# OctoSlime_Haptics_LED_Driver_Imported.net
KiCad netlist of a schematic drawn in EasyEDA Pro
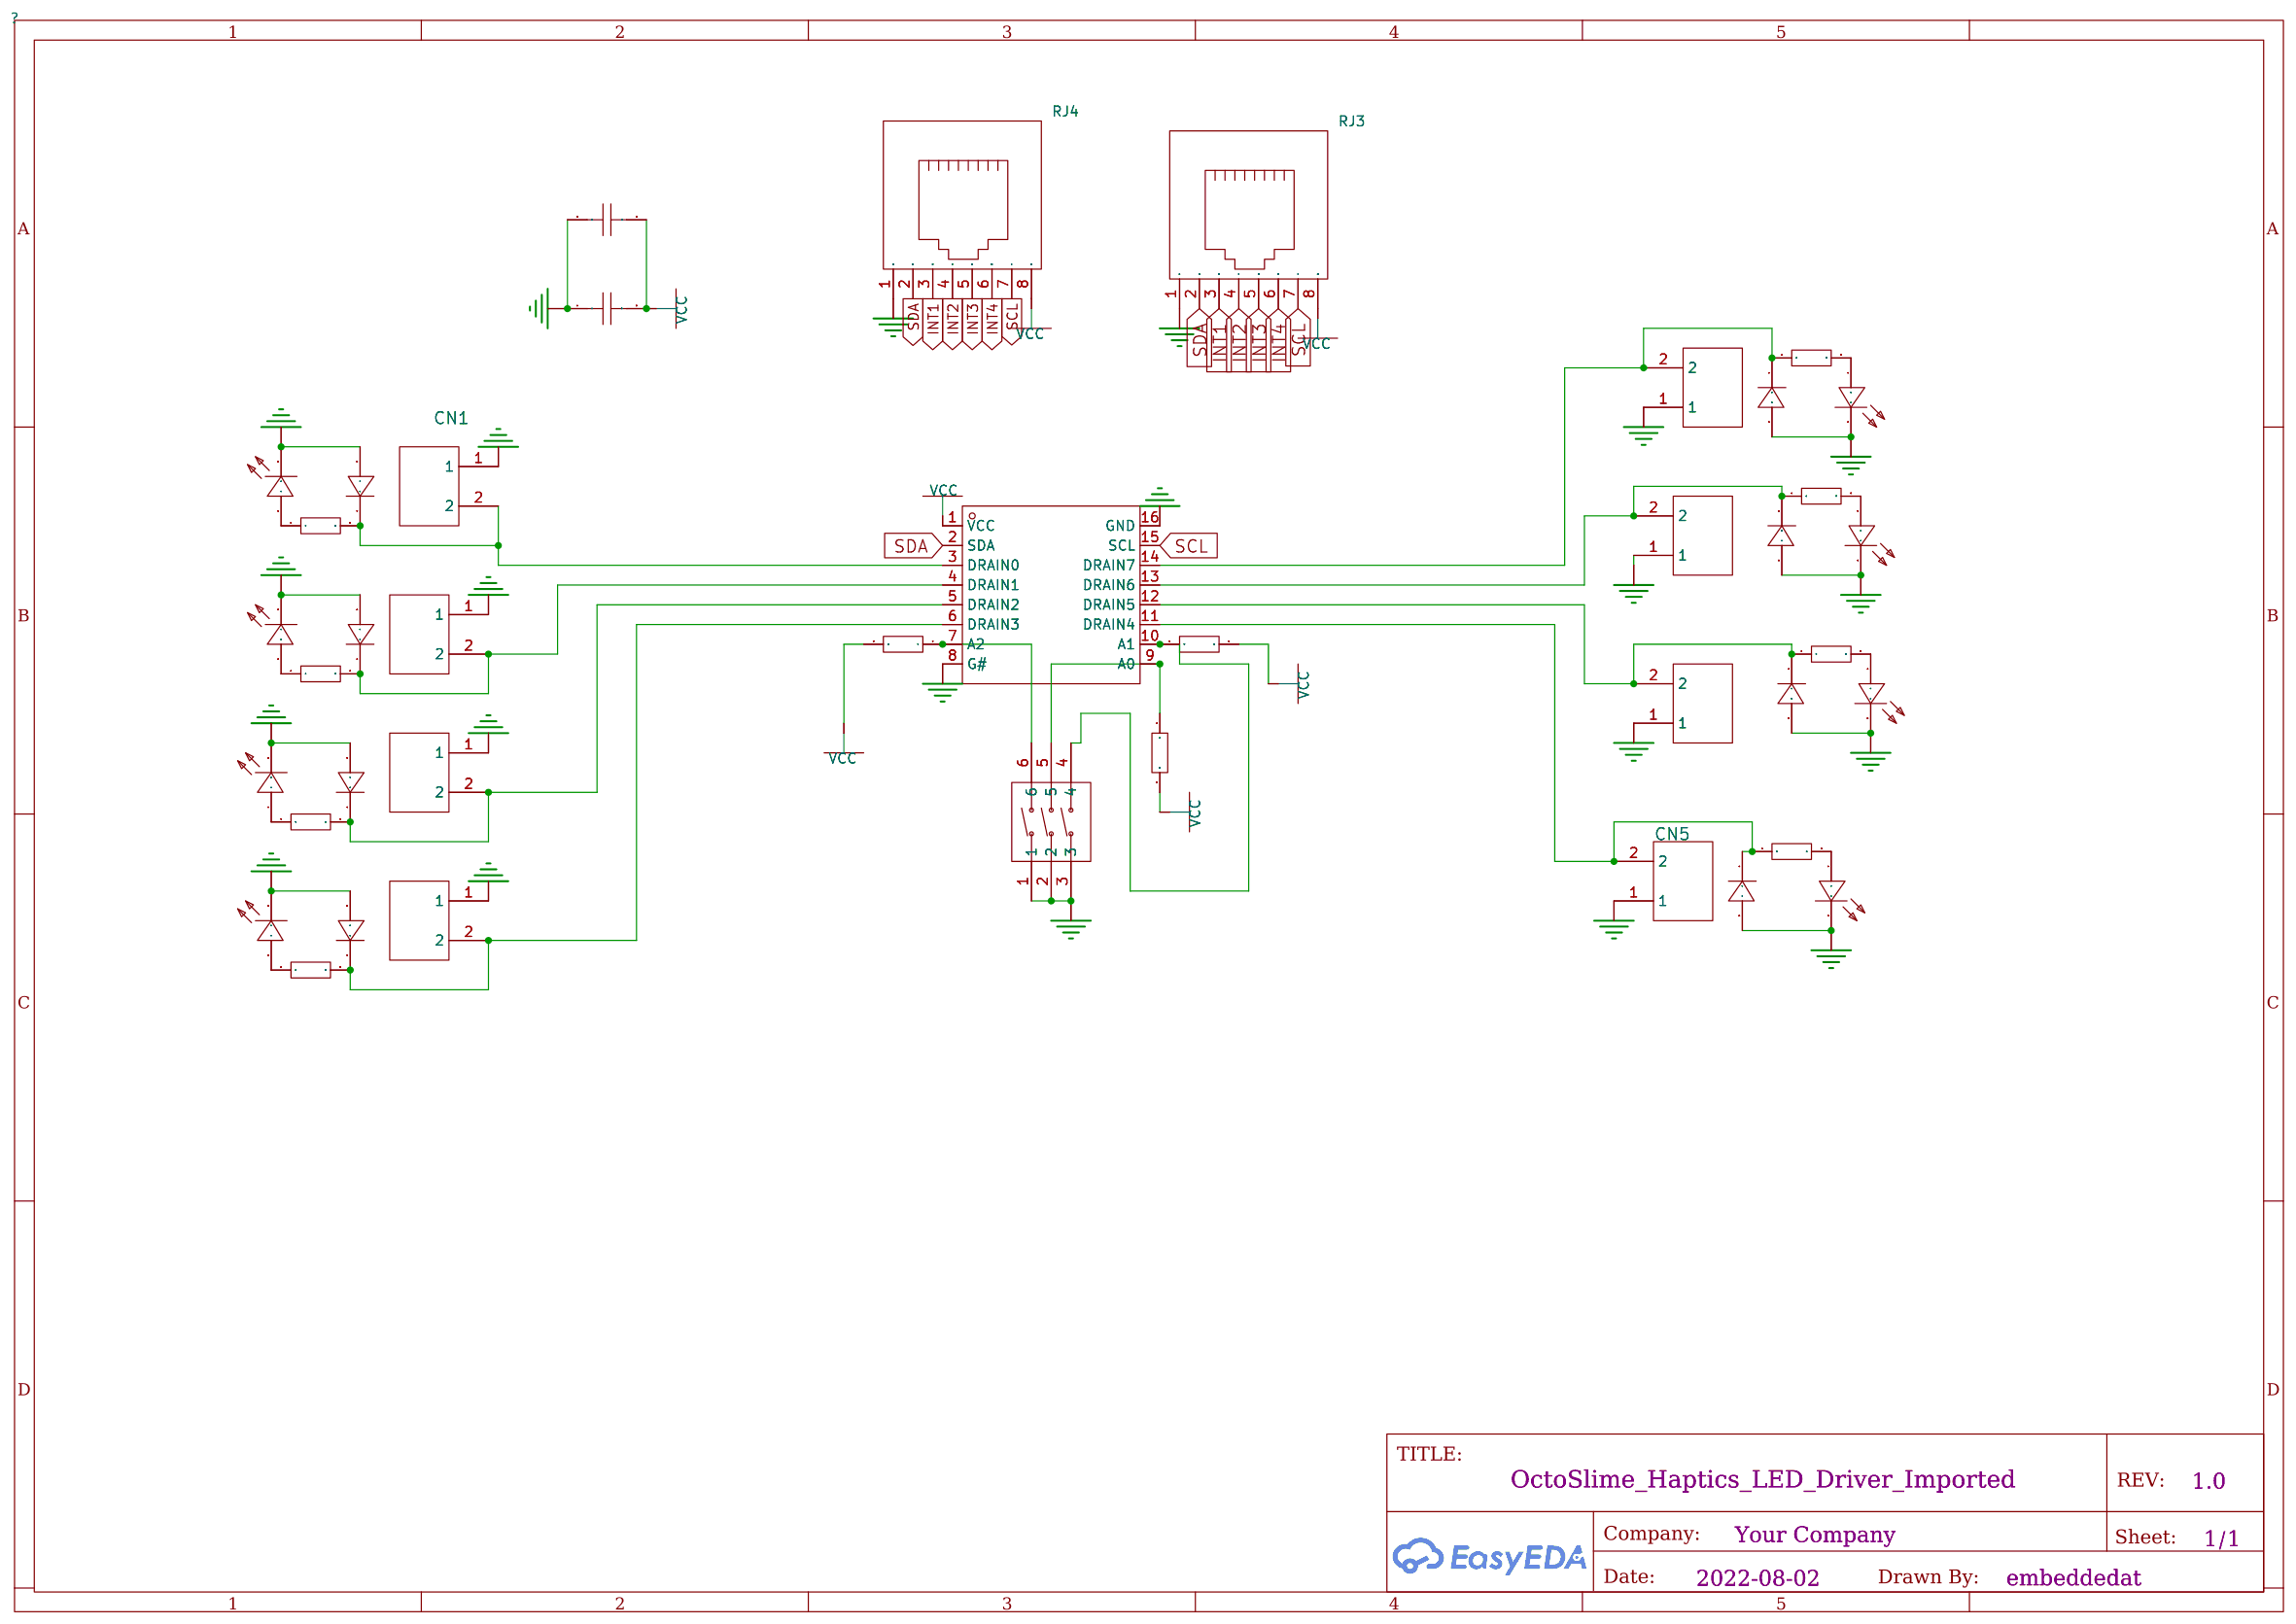
[diagram p0: schematic sheet]

(export (version "E")
  (design (tool "Eeschema 10.0.6"))
  (components
    (comp (ref "C3")
      (value "47uF")
      (footprint "easyedapro:C1206")
      (description "容值:47uF;精度:±20%;额定电压:10V;温度系数:X5R;")
      (fields
        (field (name "Manufacturer Part") "CL31A476MPHNNNE")
        (field (name "Manufacturer") "SAMSUNG(三星)")
      )
      (libsource (lib "easyedapro") (part "CL31A476MPHNNNE"))
    )
    (comp (ref "C4")
      (value "100nF")
      (footprint "easyedapro:C0402")
      (description "容值:100nF;精度:±10%;额定电压:50V;温度系数:X7R;")
      (fields
        (field (name "Manufacturer Part") "CL05B104KB54PNC")
        (field (name "Manufacturer") "SAMSUNG(三星)")
      )
      (libsource (lib "easyedapro") (part "CL05B104KB54PNC"))
    )
    (comp (ref "CN1")
      (value "B2B-PH-K-S(LF)(SN)")
      (footprint "easyedapro:CONN-TH_B2B-PH-K-S")
      (fields (field (name "Manufacturer") "JST"))
      (libsource (lib "easyedapro") (part "B2B-PH-K-S(LF)(SN)"))
    )
    (comp (ref "CN2")
      (value "B2B-PH-K-S(LF)(SN)")
      (footprint "easyedapro:CONN-TH_B2B-PH-K-S")
      (fields (field (name "Manufacturer") "JST"))
      (libsource (lib "easyedapro") (part "B2B-PH-K-S(LF)(SN)"))
    )
    (comp (ref "CN3")
      (value "B2B-PH-K-S(LF)(SN)")
      (footprint "easyedapro:CONN-TH_B2B-PH-K-S")
      (fields (field (name "Manufacturer") "JST"))
      (libsource (lib "easyedapro") (part "B2B-PH-K-S(LF)(SN)"))
    )
    (comp (ref "CN4")
      (value "B2B-PH-K-S(LF)(SN)")
      (footprint "easyedapro:CONN-TH_B2B-PH-K-S")
      (fields (field (name "Manufacturer") "JST"))
      (libsource (lib "easyedapro") (part "B2B-PH-K-S(LF)(SN)"))
    )
    (comp (ref "CN5")
      (value "B2B-PH-K-S(LF)(SN)")
      (footprint "easyedapro:CONN-TH_B2B-PH-K-S")
      (fields (field (name "Manufacturer") "JST"))
      (libsource (lib "easyedapro") (part "B2B-PH-K-S(LF)(SN)"))
    )
    (comp (ref "CN6")
      (value "B2B-PH-K-S(LF)(SN)")
      (footprint "easyedapro:CONN-TH_B2B-PH-K-S")
      (fields (field (name "Manufacturer") "JST"))
      (libsource (lib "easyedapro") (part "B2B-PH-K-S(LF)(SN)"))
    )
    (comp (ref "CN7")
      (value "B2B-PH-K-S(LF)(SN)")
      (footprint "easyedapro:CONN-TH_B2B-PH-K-S")
      (fields (field (name "Manufacturer") "JST"))
      (libsource (lib "easyedapro") (part "B2B-PH-K-S(LF)(SN)"))
    )
    (comp (ref "CN8")
      (value "B2B-PH-K-S(LF)(SN)")
      (footprint "easyedapro:CONN-TH_B2B-PH-K-S")
      (fields (field (name "Manufacturer") "JST"))
      (libsource (lib "easyedapro") (part "B2B-PH-K-S(LF)(SN)"))
    )
    (comp (ref "D9")
      (value "~")
      (footprint "easyedapro:DO-214AC_L4.3-W2.7-LS5.3-RD")
      (description "二极管配置:-;直流反向耐压(Vr):1kV;平均整流电流(Io):1A;正向压降(Vf):1.1V@1A;反向电流(Ir):5A@1kV;")
      (fields (field (name "Manufacturer Part") "M7") (field (name "Manufacturer") "MDD"))
      (libsource (lib "easyedapro") (part "M7_C95872"))
    )
    (comp (ref "D10")
      (value "~")
      (footprint "easyedapro:DO-214AC_L4.3-W2.7-LS5.3-RD")
      (description "二极管配置:-;直流反向耐压(Vr):1kV;平均整流电流(Io):1A;正向压降(Vf):1.1V@1A;反向电流(Ir):5A@1kV;")
      (fields (field (name "Manufacturer Part") "M7") (field (name "Manufacturer") "MDD"))
      (libsource (lib "easyedapro") (part "M7_C95872"))
    )
    (comp (ref "D11")
      (value "~")
      (footprint "easyedapro:DO-214AC_L4.3-W2.7-LS5.3-RD")
      (description "二极管配置:-;直流反向耐压(Vr):1kV;平均整流电流(Io):1A;正向压降(Vf):1.1V@1A;反向电流(Ir):5A@1kV;")
      (fields (field (name "Manufacturer Part") "M7") (field (name "Manufacturer") "MDD"))
      (libsource (lib "easyedapro") (part "M7_C95872"))
    )
    (comp (ref "D12")
      (value "~")
      (footprint "easyedapro:DO-214AC_L4.3-W2.7-LS5.3-RD")
      (description "二极管配置:-;直流反向耐压(Vr):1kV;平均整流电流(Io):1A;正向压降(Vf):1.1V@1A;反向电流(Ir):5A@1kV;")
      (fields (field (name "Manufacturer Part") "M7") (field (name "Manufacturer") "MDD"))
      (libsource (lib "easyedapro") (part "M7_C95872"))
    )
    (comp (ref "D13")
      (value "~")
      (footprint "easyedapro:DO-214AC_L4.3-W2.7-LS5.3-RD")
      (description "二极管配置:-;直流反向耐压(Vr):1kV;平均整流电流(Io):1A;正向压降(Vf):1.1V@1A;反向电流(Ir):5A@1kV;")
      (fields (field (name "Manufacturer Part") "M7") (field (name "Manufacturer") "MDD"))
      (libsource (lib "easyedapro") (part "M7_C95872"))
    )
    (comp (ref "D14")
      (value "~")
      (footprint "easyedapro:DO-214AC_L4.3-W2.7-LS5.3-RD")
      (description "二极管配置:-;直流反向耐压(Vr):1kV;平均整流电流(Io):1A;正向压降(Vf):1.1V@1A;反向电流(Ir):5A@1kV;")
      (fields (field (name "Manufacturer Part") "M7") (field (name "Manufacturer") "MDD"))
      (libsource (lib "easyedapro") (part "M7_C95872"))
    )
    (comp (ref "D15")
      (value "~")
      (footprint "easyedapro:DO-214AC_L4.3-W2.7-LS5.3-RD")
      (description "二极管配置:-;直流反向耐压(Vr):1kV;平均整流电流(Io):1A;正向压降(Vf):1.1V@1A;反向电流(Ir):5A@1kV;")
      (fields (field (name "Manufacturer Part") "M7") (field (name "Manufacturer") "MDD"))
      (libsource (lib "easyedapro") (part "M7_C95872"))
    )
    (comp (ref "D16")
      (value "~")
      (footprint "easyedapro:DO-214AC_L4.3-W2.7-LS5.3-RD")
      (description "二极管配置:-;直流反向耐压(Vr):1kV;平均整流电流(Io):1A;正向压降(Vf):1.1V@1A;反向电流(Ir):5A@1kV;")
      (fields (field (name "Manufacturer Part") "M7") (field (name "Manufacturer") "MDD"))
      (libsource (lib "easyedapro") (part "M7_C95872"))
    )
    (comp (ref "LED9")
      (value "~")
      (footprint "easyedapro:LED0603-R-RD")
      (fields (field (name "Manufacturer Part") "KT-0603R") (field (name "Manufacturer") "KENTO"))
      (libsource (lib "easyedapro") (part "KT-0603R"))
    )
    (comp (ref "LED10")
      (value "~")
      (footprint "easyedapro:LED0603-R-RD")
      (fields (field (name "Manufacturer Part") "KT-0603R") (field (name "Manufacturer") "KENTO"))
      (libsource (lib "easyedapro") (part "KT-0603R"))
    )
    (comp (ref "LED11")
      (value "~")
      (footprint "easyedapro:LED0603-R-RD")
      (fields (field (name "Manufacturer Part") "KT-0603R") (field (name "Manufacturer") "KENTO"))
      (libsource (lib "easyedapro") (part "KT-0603R"))
    )
    (comp (ref "LED12")
      (value "~")
      (footprint "easyedapro:LED0603-R-RD")
      (fields (field (name "Manufacturer Part") "KT-0603R") (field (name "Manufacturer") "KENTO"))
      (libsource (lib "easyedapro") (part "KT-0603R"))
    )
    (comp (ref "LED13")
      (value "~")
      (footprint "easyedapro:LED0603-R-RD")
      (fields (field (name "Manufacturer Part") "KT-0603R") (field (name "Manufacturer") "KENTO"))
      (libsource (lib "easyedapro") (part "KT-0603R"))
    )
    (comp (ref "LED14")
      (value "~")
      (footprint "easyedapro:LED0603-R-RD")
      (fields (field (name "Manufacturer Part") "KT-0603R") (field (name "Manufacturer") "KENTO"))
      (libsource (lib "easyedapro") (part "KT-0603R"))
    )
    (comp (ref "LED15")
      (value "~")
      (footprint "easyedapro:LED0603-R-RD")
      (fields (field (name "Manufacturer Part") "KT-0603R") (field (name "Manufacturer") "KENTO"))
      (libsource (lib "easyedapro") (part "KT-0603R"))
    )
    (comp (ref "LED16")
      (value "~")
      (footprint "easyedapro:LED0603-R-RD")
      (fields (field (name "Manufacturer Part") "KT-0603R") (field (name "Manufacturer") "KENTO"))
      (libsource (lib "easyedapro") (part "KT-0603R"))
    )
    (comp (ref "R1")
      (value "1kΩ")
      (footprint "easyedapro:R0603")
      (description "电阻类型:厚膜电阻;阻值:1kΩ;精度:±1%;功率:1/10W;温度系数:±100ppm/;最大工作电压:75V;工作温度范围:-55~+155;")
      (fields
        (field (name "Manufacturer Part") "0603WAF1001T5E")
        (field (name "Manufacturer") "UNI-ROYAL(厚声)")
      )
      (libsource (lib "easyedapro") (part "0603WAF1001T5E"))
    )
    (comp (ref "R2")
      (value "1kΩ")
      (footprint "easyedapro:R0603")
      (description "电阻类型:厚膜电阻;阻值:1kΩ;精度:±1%;功率:1/10W;温度系数:±100ppm/;最大工作电压:75V;工作温度范围:-55~+155;")
      (fields
        (field (name "Manufacturer Part") "0603WAF1001T5E")
        (field (name "Manufacturer") "UNI-ROYAL(厚声)")
      )
      (libsource (lib "easyedapro") (part "0603WAF1001T5E"))
    )
    (comp (ref "R12")
      (value "330Ω")
      (footprint "easyedapro:R0603")
      (description "电阻类型:厚膜电阻;阻值:330Ω;精度:±1%;功率:1/10W;温度系数:±100ppm/;最大工作电压:75V;工作温度范围:-55~+155;")
      (fields
        (field (name "Manufacturer Part") "0603WAF3300T5E")
        (field (name "Manufacturer") "UNI-ROYAL(厚声)")
      )
      (libsource (lib "easyedapro") (part "0603WAF3300T5E"))
    )
    (comp (ref "R13")
      (value "330Ω")
      (footprint "easyedapro:R0603")
      (description "电阻类型:厚膜电阻;阻值:330Ω;精度:±1%;功率:1/10W;温度系数:±100ppm/;最大工作电压:75V;工作温度范围:-55~+155;")
      (fields
        (field (name "Manufacturer Part") "0603WAF3300T5E")
        (field (name "Manufacturer") "UNI-ROYAL(厚声)")
      )
      (libsource (lib "easyedapro") (part "0603WAF3300T5E"))
    )
    (comp (ref "R14")
      (value "330Ω")
      (footprint "easyedapro:R0603")
      (description "电阻类型:厚膜电阻;阻值:330Ω;精度:±1%;功率:1/10W;温度系数:±100ppm/;最大工作电压:75V;工作温度范围:-55~+155;")
      (fields
        (field (name "Manufacturer Part") "0603WAF3300T5E")
        (field (name "Manufacturer") "UNI-ROYAL(厚声)")
      )
      (libsource (lib "easyedapro") (part "0603WAF3300T5E"))
    )
    (comp (ref "R15")
      (value "330Ω")
      (footprint "easyedapro:R0603")
      (description "电阻类型:厚膜电阻;阻值:330Ω;精度:±1%;功率:1/10W;温度系数:±100ppm/;最大工作电压:75V;工作温度范围:-55~+155;")
      (fields
        (field (name "Manufacturer Part") "0603WAF3300T5E")
        (field (name "Manufacturer") "UNI-ROYAL(厚声)")
      )
      (libsource (lib "easyedapro") (part "0603WAF3300T5E"))
    )
    (comp (ref "R16")
      (value "330Ω")
      (footprint "easyedapro:R0603")
      (description "电阻类型:厚膜电阻;阻值:330Ω;精度:±1%;功率:1/10W;温度系数:±100ppm/;最大工作电压:75V;工作温度范围:-55~+155;")
      (fields
        (field (name "Manufacturer Part") "0603WAF3300T5E")
        (field (name "Manufacturer") "UNI-ROYAL(厚声)")
      )
      (libsource (lib "easyedapro") (part "0603WAF3300T5E"))
    )
    (comp (ref "R17")
      (value "330Ω")
      (footprint "easyedapro:R0603")
      (description "电阻类型:厚膜电阻;阻值:330Ω;精度:±1%;功率:1/10W;温度系数:±100ppm/;最大工作电压:75V;工作温度范围:-55~+155;")
      (fields
        (field (name "Manufacturer Part") "0603WAF3300T5E")
        (field (name "Manufacturer") "UNI-ROYAL(厚声)")
      )
      (libsource (lib "easyedapro") (part "0603WAF3300T5E"))
    )
    (comp (ref "R18")
      (value "330Ω")
      (footprint "easyedapro:R0603")
      (description "电阻类型:厚膜电阻;阻值:330Ω;精度:±1%;功率:1/10W;温度系数:±100ppm/;最大工作电压:75V;工作温度范围:-55~+155;")
      (fields
        (field (name "Manufacturer Part") "0603WAF3300T5E")
        (field (name "Manufacturer") "UNI-ROYAL(厚声)")
      )
      (libsource (lib "easyedapro") (part "0603WAF3300T5E"))
    )
    (comp (ref "R19")
      (value "330Ω")
      (footprint "easyedapro:R0603")
      (description "电阻类型:厚膜电阻;阻值:330Ω;精度:±1%;功率:1/10W;温度系数:±100ppm/;最大工作电压:75V;工作温度范围:-55~+155;")
      (fields
        (field (name "Manufacturer Part") "0603WAF3300T5E")
        (field (name "Manufacturer") "UNI-ROYAL(厚声)")
      )
      (libsource (lib "easyedapro") (part "0603WAF3300T5E"))
    )
    (comp (ref "R20")
      (value "1kΩ")
      (footprint "easyedapro:R0603")
      (description "电阻类型:厚膜电阻;阻值:1kΩ;精度:±1%;功率:1/10W;温度系数:±100ppm/;最大工作电压:75V;工作温度范围:-55~+155;")
      (fields
        (field (name "Manufacturer Part") "0603WAF1001T5E")
        (field (name "Manufacturer") "UNI-ROYAL(厚声)")
      )
      (libsource (lib "easyedapro") (part "0603WAF1001T5E"))
    )
    (comp (ref "RJ3")
      (value "~")
      (footprint "easyedapro:RJ45-TH_R-RJ45R08P-A004")
      (description "连接器类型:RJ插座;USOC代码:RJ45;端口数量:1;等级:-;安装方式:弯插;屏蔽:无;LED:无;工作温度范围:0~+70;")
      (fields (field (name "Manufacturer Part") "R-RJ45R08P-A004") (field (name "Manufacturer") "Ckmtw(灿科盟)"))
      (libsource (lib "easyedapro") (part "R-RJ45R08P-A004"))
    )
    (comp (ref "RJ4")
      (value "~")
      (footprint "easyedapro:RJ45-TH_R-RJ45R08P-A004")
      (description "连接器类型:RJ插座;USOC代码:RJ45;端口数量:1;等级:-;安装方式:弯插;屏蔽:无;LED:无;工作温度范围:0~+70;")
      (fields (field (name "Manufacturer Part") "R-RJ45R08P-A004") (field (name "Manufacturer") "Ckmtw(灿科盟)"))
      (libsource (lib "easyedapro") (part "R-RJ45R08P-A004"))
    )
    (comp (ref "SW1")
      (value "EM-03KP")
      (footprint "easyedapro:SW-SMD_EM-03KP")
      (fields (field (name "Manufacturer") "HRO"))
      (libsource (lib "easyedapro") (part "EM-03KP"))
    )
    (comp (ref "U1")
      (value "TPIC2810DRG4")
      (footprint "easyedapro:SOIC-16_L9.9-W3.9-P1.27-LS6.0-BL")
      (fields (field (name "Manufacturer") "TI(德州仪器)"))
      (libsource (lib "easyedapro") (part "TPIC2810DRG4"))
    )
  )
  (nets
    (net (code "1") (name "GND") (class "Default")
      (node (ref "C3") (pin "1") (pinfunction "1_1") (pintype "input"))
      (node (ref "C4") (pin "1") (pinfunction "1_1") (pintype "input"))
      (node (ref "CN1") (pin "1") (pinfunction "1_1") (pintype "input"))
      (node (ref "CN2") (pin "1") (pinfunction "1_1") (pintype "input"))
      (node (ref "CN3") (pin "1") (pinfunction "1_1") (pintype "input"))
      (node (ref "CN4") (pin "1") (pinfunction "1_1") (pintype "input"))
      (node (ref "CN5") (pin "1") (pinfunction "1_1") (pintype "input"))
      (node (ref "CN6") (pin "1") (pinfunction "1_1") (pintype "input"))
      (node (ref "CN7") (pin "1") (pinfunction "1_1") (pintype "input"))
      (node (ref "CN8") (pin "1") (pinfunction "1_1") (pintype "input"))
      (node (ref "D10") (pin "2") (pinfunction "A_2") (pintype "input"))
      (node (ref "D11") (pin "2") (pinfunction "A_2") (pintype "input"))
      (node (ref "D12") (pin "2") (pinfunction "A_2") (pintype "input"))
      (node (ref "D13") (pin "2") (pinfunction "A_2") (pintype "input"))
      (node (ref "D14") (pin "2") (pinfunction "A_2") (pintype "input"))
      (node (ref "D15") (pin "2") (pinfunction "A_2") (pintype "input"))
      (node (ref "D16") (pin "2") (pinfunction "A_2") (pintype "input"))
      (node (ref "D9") (pin "2") (pinfunction "A_2") (pintype "input"))
      (node (ref "LED10") (pin "2") (pinfunction "K_2") (pintype "input"))
      (node (ref "LED11") (pin "2") (pinfunction "K_2") (pintype "input"))
      (node (ref "LED12") (pin "2") (pinfunction "K_2") (pintype "input"))
      (node (ref "LED13") (pin "2") (pinfunction "K_2") (pintype "input"))
      (node (ref "LED14") (pin "2") (pinfunction "K_2") (pintype "input"))
      (node (ref "LED15") (pin "2") (pinfunction "K_2") (pintype "input"))
      (node (ref "LED16") (pin "2") (pinfunction "K_2") (pintype "input"))
      (node (ref "LED9") (pin "2") (pinfunction "K_2") (pintype "input"))
      (node (ref "RJ3") (pin "1") (pinfunction "1_1") (pintype "input"))
      (node (ref "RJ4") (pin "1") (pinfunction "1_1") (pintype "input"))
      (node (ref "SW1") (pin "1") (pinfunction "1_1") (pintype "input"))
      (node (ref "SW1") (pin "2") (pinfunction "2_2") (pintype "input"))
      (node (ref "SW1") (pin "3") (pinfunction "3_3") (pintype "input"))
      (node (ref "U1") (pin "16") (pinfunction "GND_16") (pintype "input"))
      (node (ref "U1") (pin "8") (pinfunction "G#_8") (pintype "input"))
    )
    (net (code "2") (name "INT1") (class "Default")
      (node (ref "RJ3") (pin "3") (pinfunction "3_3") (pintype "input"))
      (node (ref "RJ4") (pin "3") (pinfunction "3_3") (pintype "input"))
    )
    (net (code "3") (name "INT2") (class "Default")
      (node (ref "RJ3") (pin "4") (pinfunction "4_4") (pintype "input"))
      (node (ref "RJ4") (pin "4") (pinfunction "4_4") (pintype "input"))
    )
    (net (code "4") (name "INT3") (class "Default")
      (node (ref "RJ3") (pin "5") (pinfunction "5_5") (pintype "input"))
      (node (ref "RJ4") (pin "5") (pinfunction "5_5") (pintype "input"))
    )
    (net (code "5") (name "INT4") (class "Default")
      (node (ref "RJ3") (pin "6") (pinfunction "6_6") (pintype "input"))
      (node (ref "RJ4") (pin "6") (pinfunction "6_6") (pintype "input"))
    )
    (net (code "6") (name "Net-(D9-K)") (class "Default")
      (node (ref "CN5") (pin "2") (pinfunction "2_2") (pintype "input"))
      (node (ref "D9") (pin "1") (pinfunction "K_1") (pintype "input"))
      (node (ref "R15") (pin "1") (pinfunction "1_1") (pintype "input"))
      (node (ref "U1") (pin "11") (pinfunction "DRAIN4_11") (pintype "input"))
    )
    (net (code "7") (name "Net-(D10-K)") (class "Default")
      (node (ref "CN6") (pin "2") (pinfunction "2_2") (pintype "input"))
      (node (ref "D10") (pin "1") (pinfunction "K_1") (pintype "input"))
      (node (ref "R14") (pin "1") (pinfunction "1_1") (pintype "input"))
      (node (ref "U1") (pin "12") (pinfunction "DRAIN5_12") (pintype "input"))
    )
    (net (code "8") (name "Net-(D11-K)") (class "Default")
      (node (ref "CN7") (pin "2") (pinfunction "2_2") (pintype "input"))
      (node (ref "D11") (pin "1") (pinfunction "K_1") (pintype "input"))
      (node (ref "R13") (pin "1") (pinfunction "1_1") (pintype "input"))
      (node (ref "U1") (pin "13") (pinfunction "DRAIN6_13") (pintype "input"))
    )
    (net (code "9") (name "Net-(D12-K)") (class "Default")
      (node (ref "CN8") (pin "2") (pinfunction "2_2") (pintype "input"))
      (node (ref "D12") (pin "1") (pinfunction "K_1") (pintype "input"))
      (node (ref "R12") (pin "1") (pinfunction "1_1") (pintype "input"))
      (node (ref "U1") (pin "14") (pinfunction "DRAIN7_14") (pintype "input"))
    )
    (net (code "10") (name "Net-(D13-K)") (class "Default")
      (node (ref "CN4") (pin "2") (pinfunction "2_2") (pintype "input"))
      (node (ref "D13") (pin "1") (pinfunction "K_1") (pintype "input"))
      (node (ref "R16") (pin "2") (pinfunction "2_2") (pintype "input"))
      (node (ref "U1") (pin "6") (pinfunction "DRAIN3_6") (pintype "input"))
    )
    (net (code "11") (name "Net-(D14-K)") (class "Default")
      (node (ref "CN3") (pin "2") (pinfunction "2_2") (pintype "input"))
      (node (ref "D14") (pin "1") (pinfunction "K_1") (pintype "input"))
      (node (ref "R17") (pin "2") (pinfunction "2_2") (pintype "input"))
      (node (ref "U1") (pin "5") (pinfunction "DRAIN2_5") (pintype "input"))
    )
    (net (code "12") (name "Net-(D15-K)") (class "Default")
      (node (ref "CN2") (pin "2") (pinfunction "2_2") (pintype "input"))
      (node (ref "D15") (pin "1") (pinfunction "K_1") (pintype "input"))
      (node (ref "R18") (pin "2") (pinfunction "2_2") (pintype "input"))
      (node (ref "U1") (pin "4") (pinfunction "DRAIN1_4") (pintype "input"))
    )
    (net (code "13") (name "Net-(D16-K)") (class "Default")
      (node (ref "CN1") (pin "2") (pinfunction "2_2") (pintype "input"))
      (node (ref "D16") (pin "1") (pinfunction "K_1") (pintype "input"))
      (node (ref "R19") (pin "2") (pinfunction "2_2") (pintype "input"))
      (node (ref "U1") (pin "3") (pinfunction "DRAIN0_3") (pintype "input"))
    )
    (net (code "14") (name "Net-(LED9-A)") (class "Default")
      (node (ref "LED9") (pin "1") (pinfunction "A_1") (pintype "input"))
      (node (ref "R12") (pin "2") (pinfunction "2_2") (pintype "input"))
    )
    (net (code "15") (name "Net-(LED10-A)") (class "Default")
      (node (ref "LED10") (pin "1") (pinfunction "A_1") (pintype "input"))
      (node (ref "R13") (pin "2") (pinfunction "2_2") (pintype "input"))
    )
    (net (code "16") (name "Net-(LED11-A)") (class "Default")
      (node (ref "LED11") (pin "1") (pinfunction "A_1") (pintype "input"))
      (node (ref "R14") (pin "2") (pinfunction "2_2") (pintype "input"))
    )
    (net (code "17") (name "Net-(LED12-A)") (class "Default")
      (node (ref "LED12") (pin "1") (pinfunction "A_1") (pintype "input"))
      (node (ref "R15") (pin "2") (pinfunction "2_2") (pintype "input"))
    )
    (net (code "18") (name "Net-(LED13-A)") (class "Default")
      (node (ref "LED13") (pin "1") (pinfunction "A_1") (pintype "input"))
      (node (ref "R19") (pin "1") (pinfunction "1_1") (pintype "input"))
    )
    (net (code "19") (name "Net-(LED14-A)") (class "Default")
      (node (ref "LED14") (pin "1") (pinfunction "A_1") (pintype "input"))
      (node (ref "R18") (pin "1") (pinfunction "1_1") (pintype "input"))
    )
    (net (code "20") (name "Net-(LED15-A)") (class "Default")
      (node (ref "LED15") (pin "1") (pinfunction "A_1") (pintype "input"))
      (node (ref "R17") (pin "1") (pinfunction "1_1") (pintype "input"))
    )
    (net (code "21") (name "Net-(LED16-A)") (class "Default")
      (node (ref "LED16") (pin "1") (pinfunction "A_1") (pintype "input"))
      (node (ref "R16") (pin "1") (pinfunction "1_1") (pintype "input"))
    )
    (net (code "22") (name "Net-(U1-A0)") (class "Default")
      (node (ref "R1") (pin "1") (pinfunction "1_1") (pintype "input"))
      (node (ref "SW1") (pin "5") (pinfunction "5_5") (pintype "input"))
      (node (ref "U1") (pin "9") (pinfunction "A0_9") (pintype "input"))
    )
    (net (code "23") (name "Net-(U1-A1)") (class "Default")
      (node (ref "R20") (pin "2") (pinfunction "2_2") (pintype "input"))
      (node (ref "SW1") (pin "4") (pinfunction "4_4") (pintype "input"))
      (node (ref "U1") (pin "10") (pinfunction "A1_10") (pintype "input"))
    )
    (net (code "24") (name "Net-(U1-A2)") (class "Default")
      (node (ref "R2") (pin "1") (pinfunction "1_1") (pintype "input"))
      (node (ref "SW1") (pin "6") (pinfunction "6_6") (pintype "input"))
      (node (ref "U1") (pin "7") (pinfunction "A2_7") (pintype "input"))
    )
    (net (code "25") (name "SCL") (class "Default")
      (node (ref "RJ3") (pin "7") (pinfunction "7_7") (pintype "input"))
      (node (ref "RJ4") (pin "7") (pinfunction "7_7") (pintype "input"))
      (node (ref "U1") (pin "15") (pinfunction "SCL_15") (pintype "input"))
    )
    (net (code "26") (name "SDA") (class "Default")
      (node (ref "RJ3") (pin "2") (pinfunction "2_2") (pintype "input"))
      (node (ref "RJ4") (pin "2") (pinfunction "2_2") (pintype "input"))
      (node (ref "U1") (pin "2") (pinfunction "SDA_2") (pintype "input"))
    )
    (net (code "27") (name "VCC") (class "Default")
      (node (ref "C3") (pin "2") (pinfunction "2_2") (pintype "input"))
      (node (ref "C4") (pin "2") (pinfunction "2_2") (pintype "input"))
      (node (ref "R1") (pin "2") (pinfunction "2_2") (pintype "input"))
      (node (ref "R2") (pin "2") (pinfunction "2_2") (pintype "input"))
      (node (ref "R20") (pin "1") (pinfunction "1_1") (pintype "input"))
      (node (ref "RJ3") (pin "8") (pinfunction "8_8") (pintype "input"))
      (node (ref "RJ4") (pin "8") (pinfunction "8_8") (pintype "input"))
      (node (ref "U1") (pin "1") (pinfunction "VCC_1") (pintype "input"))
    )
  )
)
